# usb_radio.net
KiCad netlist of a schematic drawn in EAGLE
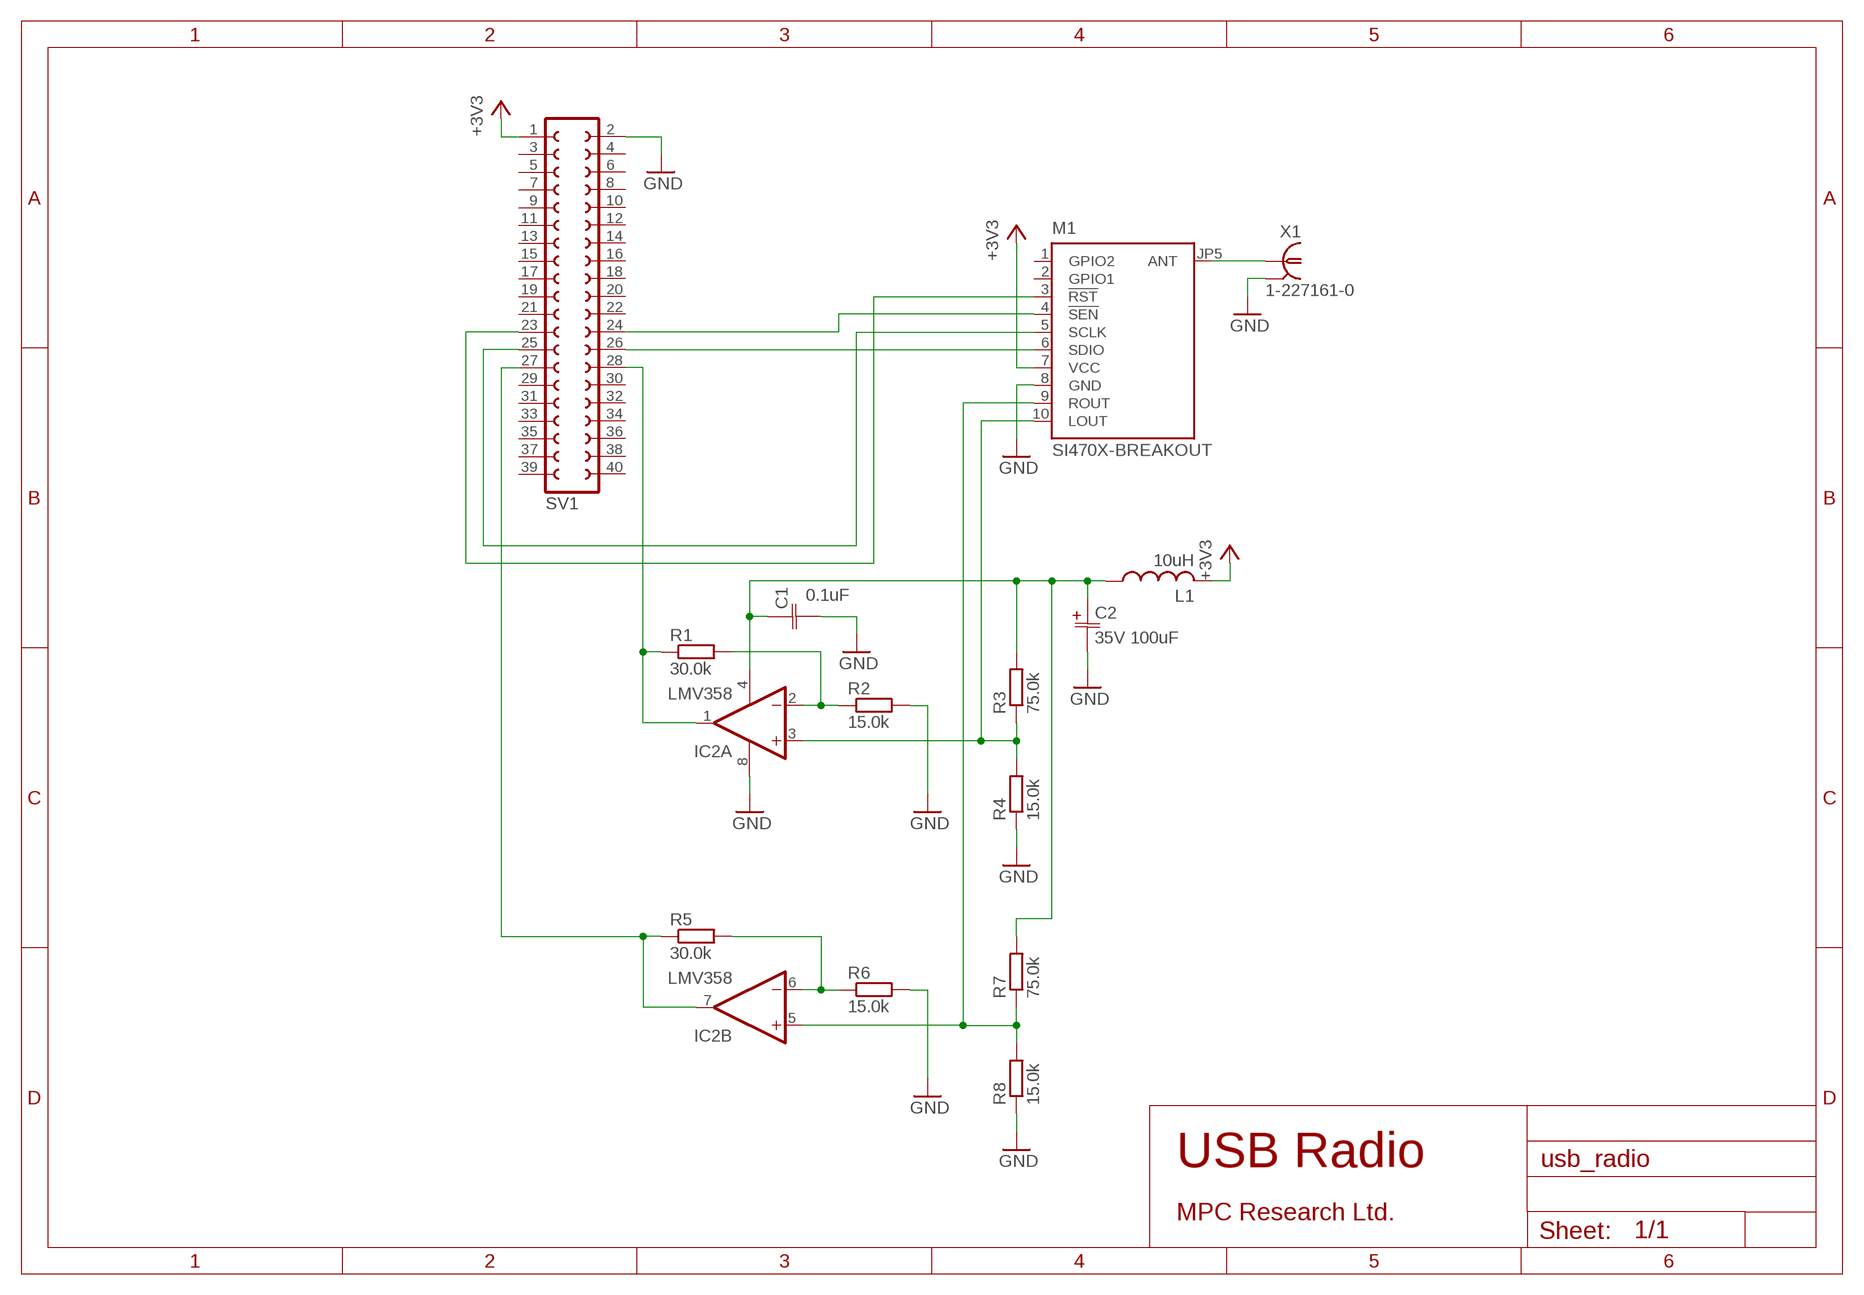
[diagram p0: schematic, sheet 1]

(export (version "E")
  (design (tool "Eeschema 10.0.6"))
  (components
    (comp (ref "C1")
      (value "0.1uF")
      (footprint "eagle-import:C050-024X044")
      (libsource (lib "eagle-import") (part "C-JIS050-024X044"))
    )
    (comp (ref "C2")
      (value "35V 100uF")
      (footprint "eagle-import:E2,5-5")
      (libsource (lib "eagle-import") (part "CPOL-JIS"))
    )
    (comp (ref "IC2")
      (value "LMV358")
      (footprint "eagle-import:SO08")
      (libsource (lib "eagle-import") (part "LMV358?M"))
    )
    (comp (ref "L1")
      (value "10uH")
      (footprint "eagle-import:0207_10")
      (libsource (lib "eagle-import") (part "L-US0207/10"))
    )
    (comp (ref "M1")
      (value "SI470X-BREAKOUT")
      (footprint "eagle-import:SI470X-BREAKOUT")
      (libsource (lib "eagle-import") (part "SI470X-BREAKOUT"))
    )
    (comp (ref "R1")
      (value "30.0k")
      (footprint "eagle-import:0207_10")
      (libsource (lib "eagle-import") (part "R-EU_0207/10"))
    )
    (comp (ref "R2")
      (value "15.0k")
      (footprint "eagle-import:0207_10")
      (libsource (lib "eagle-import") (part "R-EU_0207/10"))
    )
    (comp (ref "R3")
      (value "75.0k")
      (footprint "eagle-import:0207_10")
      (libsource (lib "eagle-import") (part "R-EU_0207/10"))
    )
    (comp (ref "R4")
      (value "15.0k")
      (footprint "eagle-import:0207_10")
      (libsource (lib "eagle-import") (part "R-EU_0207/10"))
    )
    (comp (ref "R5")
      (value "30.0k")
      (footprint "eagle-import:0207_10")
      (libsource (lib "eagle-import") (part "R-EU_0207/10"))
    )
    (comp (ref "R6")
      (value "15.0k")
      (footprint "eagle-import:0207_10")
      (libsource (lib "eagle-import") (part "R-EU_0207/10"))
    )
    (comp (ref "R7")
      (value "75.0k")
      (footprint "eagle-import:0207_10")
      (libsource (lib "eagle-import") (part "R-EU_0207/10"))
    )
    (comp (ref "R8")
      (value "15.0k")
      (footprint "eagle-import:0207_10")
      (libsource (lib "eagle-import") (part "R-EU_0207/10"))
    )
    (comp (ref "SV1")
      (value "FE20-2")
      (footprint "eagle-import:FE20-2")
      (libsource (lib "eagle-import") (part "FE20-2"))
    )
    (comp (ref "X1")
      (value "1-227161-0")
      (footprint "eagle-import:AMP_227161")
      (fields (field (name "MF") "TYCO ELECTRONICS") (field (name "MPN") "1-227161"))
      (libsource (lib "eagle-import") (part "?2271611--0"))
    )
  )
  (nets
    (net (code "1") (name "+3V3") (class "Default")
      (node (ref "L1") (pin "2") (pinfunction "2_2") (pintype "passive"))
      (node (ref "M1") (pin "7") (pinfunction "VCC_7") (pintype "power_in"))
      (node (ref "SV1") (pin "1") (pinfunction "1_1") (pintype "passive"))
    )
    (net (code "2") (name "GND") (class "Default")
      (node (ref "C1") (pin "2") (pinfunction "2_2") (pintype "passive"))
      (node (ref "C2") (pin "-") (pinfunction "-_-") (pintype "passive"))
      (node (ref "IC2") (pin "8") (pinfunction "V+_8") (pintype "power_in"))
      (node (ref "M1") (pin "8") (pinfunction "GND_8") (pintype "power_in"))
      (node (ref "R2") (pin "2") (pinfunction "2_2") (pintype "passive"))
      (node (ref "R4") (pin "1") (pinfunction "1_1") (pintype "passive"))
      (node (ref "R6") (pin "2") (pinfunction "2_2") (pintype "passive"))
      (node (ref "R8") (pin "1") (pinfunction "1_1") (pintype "passive"))
      (node (ref "SV1") (pin "2") (pinfunction "2_2") (pintype "passive"))
      (node (ref "X1") (pin "2") (pinfunction "2_2") (pintype "passive"))
    )
    (net (code "3") (name "Net-(IC2A-+IN)") (class "Default")
      (node (ref "IC2") (pin "3") (pinfunction "+IN_3") (pintype "input"))
      (node (ref "M1") (pin "10") (pinfunction "LOUT_10") (pintype "output"))
      (node (ref "R3") (pin "1") (pinfunction "1_1") (pintype "passive"))
      (node (ref "R4") (pin "2") (pinfunction "2_2") (pintype "passive"))
    )
    (net (code "4") (name "Net-(IC2A--IN)") (class "Default")
      (node (ref "IC2") (pin "2") (pinfunction "-IN_2") (pintype "input"))
      (node (ref "R1") (pin "2") (pinfunction "2_2") (pintype "passive"))
      (node (ref "R2") (pin "1") (pinfunction "1_1") (pintype "passive"))
    )
    (net (code "5") (name "Net-(IC2A-OUT)") (class "Default")
      (node (ref "IC2") (pin "1") (pinfunction "OUT_1") (pintype "output"))
      (node (ref "R1") (pin "1") (pinfunction "1_1") (pintype "passive"))
      (node (ref "SV1") (pin "28") (pinfunction "28_28") (pintype "passive"))
    )
    (net (code "6") (name "Net-(IC2B-+IN)") (class "Default")
      (node (ref "IC2") (pin "5") (pinfunction "+IN_5") (pintype "input"))
      (node (ref "M1") (pin "9") (pinfunction "ROUT_9") (pintype "output"))
      (node (ref "R7") (pin "1") (pinfunction "1_1") (pintype "passive"))
      (node (ref "R8") (pin "2") (pinfunction "2_2") (pintype "passive"))
    )
    (net (code "7") (name "Net-(IC2B--IN)") (class "Default")
      (node (ref "IC2") (pin "6") (pinfunction "-IN_6") (pintype "input"))
      (node (ref "R5") (pin "2") (pinfunction "2_2") (pintype "passive"))
      (node (ref "R6") (pin "1") (pinfunction "1_1") (pintype "passive"))
    )
    (net (code "8") (name "Net-(IC2B-OUT)") (class "Default")
      (node (ref "IC2") (pin "7") (pinfunction "OUT_7") (pintype "output"))
      (node (ref "R5") (pin "1") (pinfunction "1_1") (pintype "passive"))
      (node (ref "SV1") (pin "27") (pinfunction "27_27") (pintype "passive"))
    )
    (net (code "9") (name "Net-(IC2C-V-)") (class "Default")
      (node (ref "C1") (pin "1") (pinfunction "1_1") (pintype "passive"))
      (node (ref "C2") (pin "+") (pinfunction "+_+") (pintype "passive"))
      (node (ref "IC2") (pin "4") (pinfunction "V-_4") (pintype "power_in"))
      (node (ref "L1") (pin "1") (pinfunction "1_1") (pintype "passive"))
      (node (ref "R3") (pin "2") (pinfunction "2_2") (pintype "passive"))
      (node (ref "R7") (pin "2") (pinfunction "2_2") (pintype "passive"))
    )
    (net (code "10") (name "Net-(M1-ANT)") (class "Default")
      (node (ref "M1") (pin "JP5") (pinfunction "ANT_JP5") (pintype "passive"))
      (node (ref "X1") (pin "1") (pinfunction "1_1") (pintype "passive"))
    )
    (net (code "11") (name "Net-(M1-SCLK)") (class "Default")
      (node (ref "M1") (pin "5") (pinfunction "SCLK_5") (pintype "input"))
      (node (ref "SV1") (pin "25") (pinfunction "25_25") (pintype "passive"))
    )
    (net (code "12") (name "Net-(M1-SDIO)") (class "Default")
      (node (ref "M1") (pin "6") (pinfunction "SDIO_6") (pintype "bidirectional"))
      (node (ref "SV1") (pin "26") (pinfunction "26_26") (pintype "passive"))
    )
    (net (code "13") (name "Net-(M1-~{RST})") (class "Default")
      (node (ref "M1") (pin "3") (pinfunction "~{RST}_3") (pintype "input"))
      (node (ref "SV1") (pin "23") (pinfunction "23_23") (pintype "passive"))
    )
    (net (code "14") (name "Net-(M1-~{SEN})") (class "Default")
      (node (ref "M1") (pin "4") (pinfunction "~{SEN}_4") (pintype "input"))
      (node (ref "SV1") (pin "24") (pinfunction "24_24") (pintype "passive"))
    )
    (net (code "15") (name "unconnected-(M1-GPIO1-Pad2)") (class "Default")
      (node (ref "M1") (pin "2") (pinfunction "GPIO1_2") (pintype "bidirectional"))
    )
    (net (code "16") (name "unconnected-(M1-GPIO2-Pad1)") (class "Default")
      (node (ref "M1") (pin "1") (pinfunction "GPIO2_1") (pintype "bidirectional"))
    )
    (net (code "17") (name "unconnected-(SV1-Pad3)") (class "Default")
      (node (ref "SV1") (pin "3") (pinfunction "3_3") (pintype "passive"))
    )
    (net (code "18") (name "unconnected-(SV1-Pad4)") (class "Default")
      (node (ref "SV1") (pin "4") (pinfunction "4_4") (pintype "passive"))
    )
    (net (code "19") (name "unconnected-(SV1-Pad5)") (class "Default")
      (node (ref "SV1") (pin "5") (pinfunction "5_5") (pintype "passive"))
    )
    (net (code "20") (name "unconnected-(SV1-Pad6)") (class "Default")
      (node (ref "SV1") (pin "6") (pinfunction "6_6") (pintype "passive"))
    )
    (net (code "21") (name "unconnected-(SV1-Pad7)") (class "Default")
      (node (ref "SV1") (pin "7") (pinfunction "7_7") (pintype "passive"))
    )
    (net (code "22") (name "unconnected-(SV1-Pad8)") (class "Default")
      (node (ref "SV1") (pin "8") (pinfunction "8_8") (pintype "passive"))
    )
    (net (code "23") (name "unconnected-(SV1-Pad9)") (class "Default")
      (node (ref "SV1") (pin "9") (pinfunction "9_9") (pintype "passive"))
    )
    (net (code "24") (name "unconnected-(SV1-Pad10)") (class "Default")
      (node (ref "SV1") (pin "10") (pinfunction "10_10") (pintype "passive"))
    )
    (net (code "25") (name "unconnected-(SV1-Pad11)") (class "Default")
      (node (ref "SV1") (pin "11") (pinfunction "11_11") (pintype "passive"))
    )
    (net (code "26") (name "unconnected-(SV1-Pad12)") (class "Default")
      (node (ref "SV1") (pin "12") (pinfunction "12_12") (pintype "passive"))
    )
    (net (code "27") (name "unconnected-(SV1-Pad13)") (class "Default")
      (node (ref "SV1") (pin "13") (pinfunction "13_13") (pintype "passive"))
    )
    (net (code "28") (name "unconnected-(SV1-Pad14)") (class "Default")
      (node (ref "SV1") (pin "14") (pinfunction "14_14") (pintype "passive"))
    )
    (net (code "29") (name "unconnected-(SV1-Pad15)") (class "Default")
      (node (ref "SV1") (pin "15") (pinfunction "15_15") (pintype "passive"))
    )
    (net (code "30") (name "unconnected-(SV1-Pad16)") (class "Default")
      (node (ref "SV1") (pin "16") (pinfunction "16_16") (pintype "passive"))
    )
    (net (code "31") (name "unconnected-(SV1-Pad17)") (class "Default")
      (node (ref "SV1") (pin "17") (pinfunction "17_17") (pintype "passive"))
    )
    (net (code "32") (name "unconnected-(SV1-Pad18)") (class "Default")
      (node (ref "SV1") (pin "18") (pinfunction "18_18") (pintype "passive"))
    )
    (net (code "33") (name "unconnected-(SV1-Pad19)") (class "Default")
      (node (ref "SV1") (pin "19") (pinfunction "19_19") (pintype "passive"))
    )
    (net (code "34") (name "unconnected-(SV1-Pad20)") (class "Default")
      (node (ref "SV1") (pin "20") (pinfunction "20_20") (pintype "passive"))
    )
    (net (code "35") (name "unconnected-(SV1-Pad21)") (class "Default")
      (node (ref "SV1") (pin "21") (pinfunction "21_21") (pintype "passive"))
    )
    (net (code "36") (name "unconnected-(SV1-Pad22)") (class "Default")
      (node (ref "SV1") (pin "22") (pinfunction "22_22") (pintype "passive"))
    )
    (net (code "37") (name "unconnected-(SV1-Pad29)") (class "Default")
      (node (ref "SV1") (pin "29") (pinfunction "29_29") (pintype "passive"))
    )
    (net (code "38") (name "unconnected-(SV1-Pad30)") (class "Default")
      (node (ref "SV1") (pin "30") (pinfunction "30_30") (pintype "passive"))
    )
    (net (code "39") (name "unconnected-(SV1-Pad31)") (class "Default")
      (node (ref "SV1") (pin "31") (pinfunction "31_31") (pintype "passive"))
    )
    (net (code "40") (name "unconnected-(SV1-Pad32)") (class "Default")
      (node (ref "SV1") (pin "32") (pinfunction "32_32") (pintype "passive"))
    )
    (net (code "41") (name "unconnected-(SV1-Pad33)") (class "Default")
      (node (ref "SV1") (pin "33") (pinfunction "33_33") (pintype "passive"))
    )
    (net (code "42") (name "unconnected-(SV1-Pad34)") (class "Default")
      (node (ref "SV1") (pin "34") (pinfunction "34_34") (pintype "passive"))
    )
    (net (code "43") (name "unconnected-(SV1-Pad35)") (class "Default")
      (node (ref "SV1") (pin "35") (pinfunction "35_35") (pintype "passive"))
    )
    (net (code "44") (name "unconnected-(SV1-Pad36)") (class "Default")
      (node (ref "SV1") (pin "36") (pinfunction "36_36") (pintype "passive"))
    )
    (net (code "45") (name "unconnected-(SV1-Pad37)") (class "Default")
      (node (ref "SV1") (pin "37") (pinfunction "37_37") (pintype "passive"))
    )
    (net (code "46") (name "unconnected-(SV1-Pad38)") (class "Default")
      (node (ref "SV1") (pin "38") (pinfunction "38_38") (pintype "passive"))
    )
    (net (code "47") (name "unconnected-(SV1-Pad39)") (class "Default")
      (node (ref "SV1") (pin "39") (pinfunction "39_39") (pintype "passive"))
    )
    (net (code "48") (name "unconnected-(SV1-Pad40)") (class "Default")
      (node (ref "SV1") (pin "40") (pinfunction "40_40") (pintype "passive"))
    )
  )
)
